# LilyPad_Rainbow_LED_v02.net
KiCad netlist of a schematic drawn in EAGLE
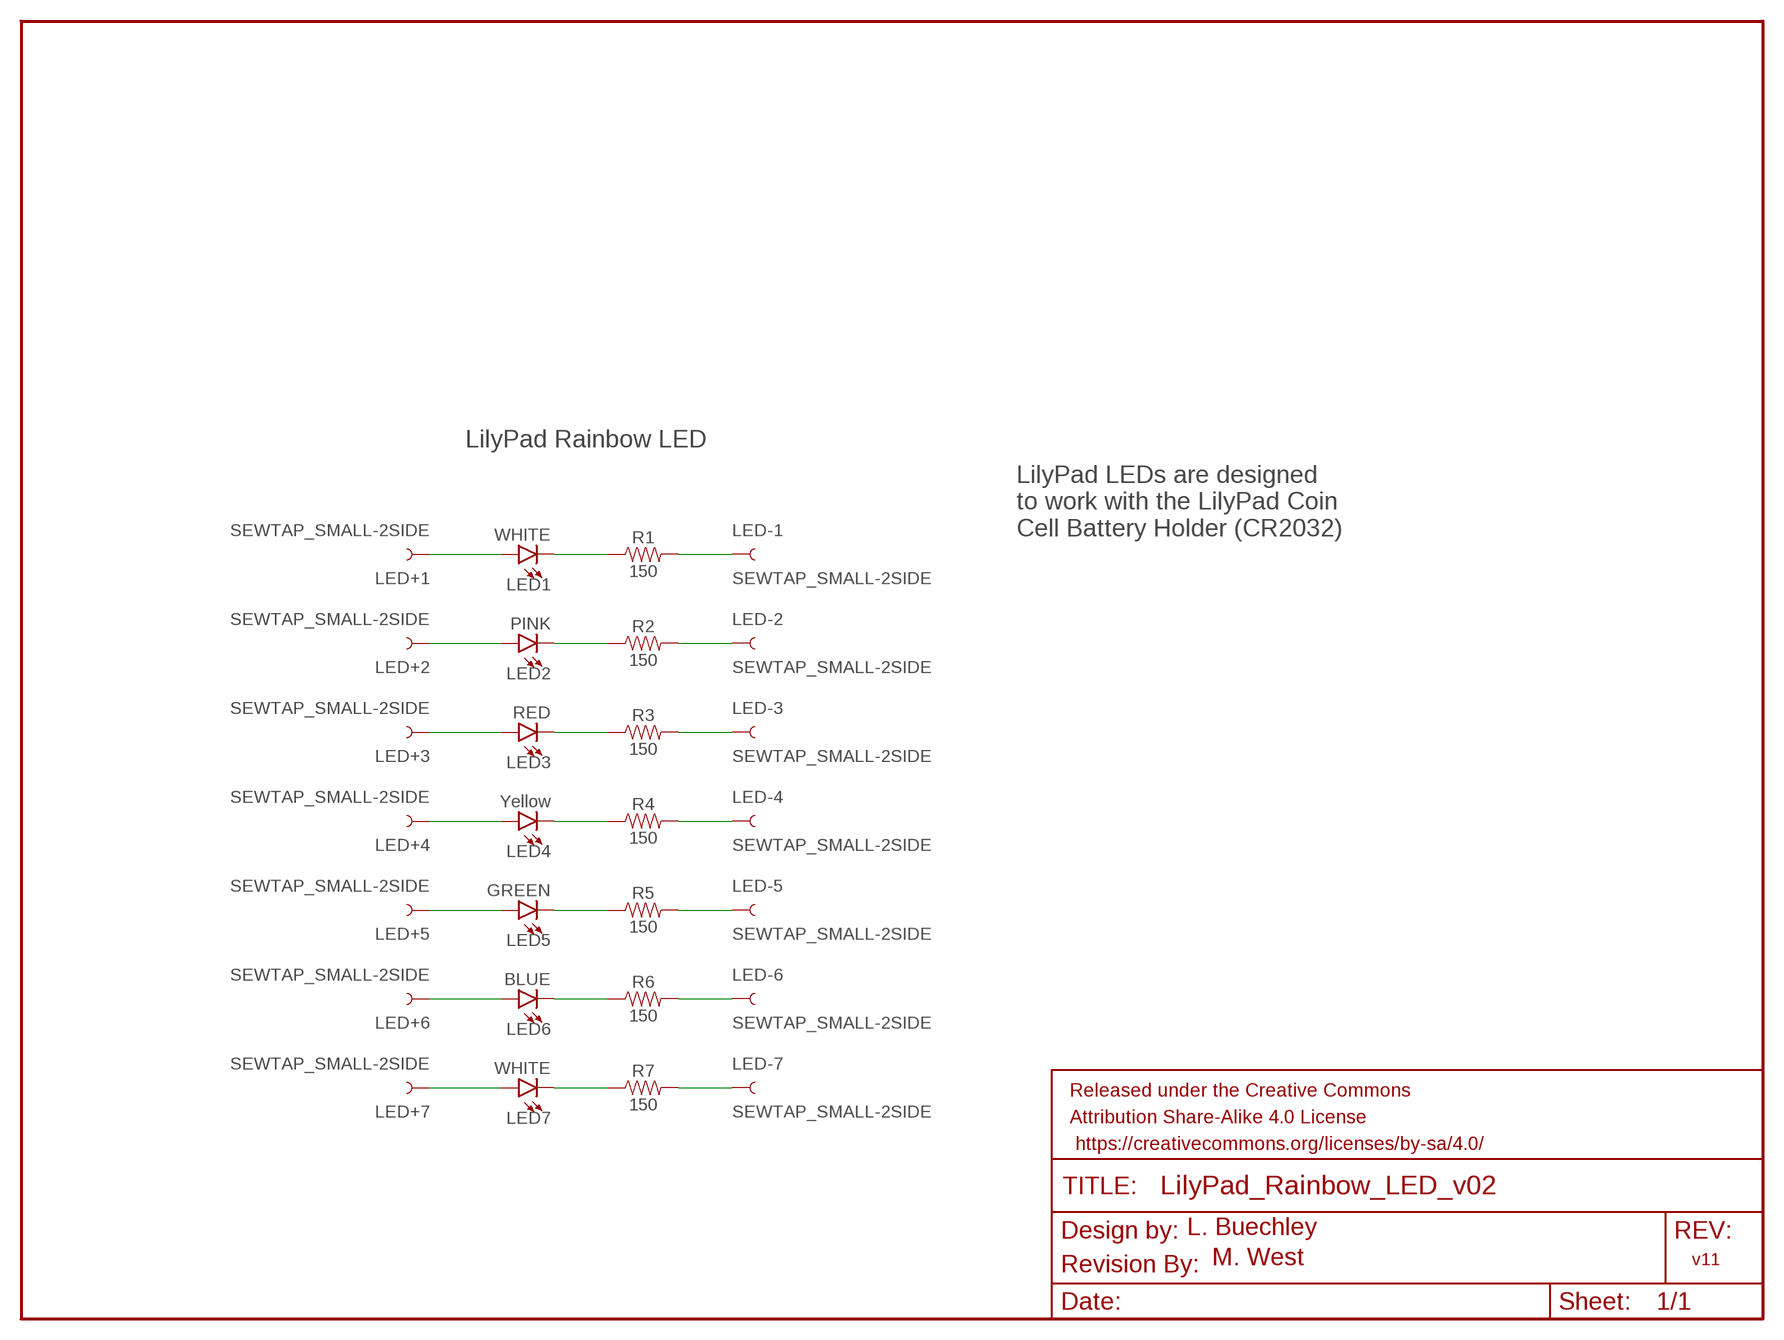
[diagram p0: schematic, sheet 1]

(export (version "E")
  (design (tool "Eeschema 10.0.6"))
  (components
    (comp (ref "FRAME1")
      (value "FRAME-LETTER")
      (footprint "eagle-import:CREATIVE_COMMONS")
      (libsource (lib "eagle-import") (part "FRAME-LETTER"))
    )
    (comp (ref "LED+1")
      (value "SEWTAP_SMALL-2SIDE")
      (footprint "eagle-import:PETAL-SMALL-2SIDE")
      (libsource (lib "eagle-import") (part "SEWTAP_SMALL-2SIDE"))
    )
    (comp (ref "LED+2")
      (value "SEWTAP_SMALL-2SIDE")
      (footprint "eagle-import:PETAL-SMALL-2SIDE")
      (libsource (lib "eagle-import") (part "SEWTAP_SMALL-2SIDE"))
    )
    (comp (ref "LED+3")
      (value "SEWTAP_SMALL-2SIDE")
      (footprint "eagle-import:PETAL-SMALL-2SIDE")
      (libsource (lib "eagle-import") (part "SEWTAP_SMALL-2SIDE"))
    )
    (comp (ref "LED+4")
      (value "SEWTAP_SMALL-2SIDE")
      (footprint "eagle-import:PETAL-SMALL-2SIDE")
      (libsource (lib "eagle-import") (part "SEWTAP_SMALL-2SIDE"))
    )
    (comp (ref "LED+5")
      (value "SEWTAP_SMALL-2SIDE")
      (footprint "eagle-import:PETAL-SMALL-2SIDE")
      (libsource (lib "eagle-import") (part "SEWTAP_SMALL-2SIDE"))
    )
    (comp (ref "LED+6")
      (value "SEWTAP_SMALL-2SIDE")
      (footprint "eagle-import:PETAL-SMALL-2SIDE")
      (libsource (lib "eagle-import") (part "SEWTAP_SMALL-2SIDE"))
    )
    (comp (ref "LED+7")
      (value "SEWTAP_SMALL-2SIDE")
      (footprint "eagle-import:PETAL-SMALL-2SIDE")
      (libsource (lib "eagle-import") (part "SEWTAP_SMALL-2SIDE"))
    )
    (comp (ref "LED-1")
      (value "SEWTAP_SMALL-2SIDE")
      (footprint "eagle-import:PETAL-SMALL-2SIDE")
      (libsource (lib "eagle-import") (part "SEWTAP_SMALL-2SIDE"))
    )
    (comp (ref "LED-2")
      (value "SEWTAP_SMALL-2SIDE")
      (footprint "eagle-import:PETAL-SMALL-2SIDE")
      (libsource (lib "eagle-import") (part "SEWTAP_SMALL-2SIDE"))
    )
    (comp (ref "LED-3")
      (value "SEWTAP_SMALL-2SIDE")
      (footprint "eagle-import:PETAL-SMALL-2SIDE")
      (libsource (lib "eagle-import") (part "SEWTAP_SMALL-2SIDE"))
    )
    (comp (ref "LED-4")
      (value "SEWTAP_SMALL-2SIDE")
      (footprint "eagle-import:PETAL-SMALL-2SIDE")
      (libsource (lib "eagle-import") (part "SEWTAP_SMALL-2SIDE"))
    )
    (comp (ref "LED-5")
      (value "SEWTAP_SMALL-2SIDE")
      (footprint "eagle-import:PETAL-SMALL-2SIDE")
      (libsource (lib "eagle-import") (part "SEWTAP_SMALL-2SIDE"))
    )
    (comp (ref "LED-6")
      (value "SEWTAP_SMALL-2SIDE")
      (footprint "eagle-import:PETAL-SMALL-2SIDE")
      (libsource (lib "eagle-import") (part "SEWTAP_SMALL-2SIDE"))
    )
    (comp (ref "LED-7")
      (value "SEWTAP_SMALL-2SIDE")
      (footprint "eagle-import:PETAL-SMALL-2SIDE")
      (libsource (lib "eagle-import") (part "SEWTAP_SMALL-2SIDE"))
    )
    (comp (ref "LED1")
      (value "WHITE")
      (footprint "eagle-import:LED-1206")
      (libsource (lib "eagle-import") (part "LED-WHITE1206"))
    )
    (comp (ref "LED2")
      (value "PINK")
      (footprint "eagle-import:LED-1206")
      (libsource (lib "eagle-import") (part "LED-PINK1206"))
    )
    (comp (ref "LED3")
      (value "RED")
      (footprint "eagle-import:LED-1206")
      (libsource (lib "eagle-import") (part "LED-RED1206"))
    )
    (comp (ref "LED4")
      (value "Yellow")
      (footprint "eagle-import:LED-1206")
      (libsource (lib "eagle-import") (part "LED-YELLOWLILYPAD"))
    )
    (comp (ref "LED5")
      (value "GREEN")
      (footprint "eagle-import:LED-1206")
      (libsource (lib "eagle-import") (part "LED-GREENLILYPAD"))
    )
    (comp (ref "LED6")
      (value "BLUE")
      (footprint "eagle-import:LED-1206")
      (libsource (lib "eagle-import") (part "LED-BLUE1206"))
    )
    (comp (ref "LED7")
      (value "WHITE")
      (footprint "eagle-import:LED-1206")
      (libsource (lib "eagle-import") (part "LED-WHITE1206"))
    )
    (comp (ref "R1")
      (value "150")
      (footprint "eagle-import:0603")
      (libsource (lib "eagle-import") (part "150OHM-0603-1/10W-1%"))
    )
    (comp (ref "R2")
      (value "150")
      (footprint "eagle-import:0603")
      (libsource (lib "eagle-import") (part "150OHM-0603-1/10W-1%"))
    )
    (comp (ref "R3")
      (value "150")
      (footprint "eagle-import:0603")
      (libsource (lib "eagle-import") (part "150OHM-0603-1/10W-1%"))
    )
    (comp (ref "R4")
      (value "150")
      (footprint "eagle-import:0603")
      (libsource (lib "eagle-import") (part "150OHM-0603-1/10W-1%"))
    )
    (comp (ref "R5")
      (value "150")
      (footprint "eagle-import:0603")
      (libsource (lib "eagle-import") (part "150OHM-0603-1/10W-1%"))
    )
    (comp (ref "R6")
      (value "150")
      (footprint "eagle-import:0603")
      (libsource (lib "eagle-import") (part "150OHM-0603-1/10W-1%"))
    )
    (comp (ref "R7")
      (value "150")
      (footprint "eagle-import:0603")
      (libsource (lib "eagle-import") (part "150OHM-0603-1/10W-1%"))
    )
    (comp (ref "U$1")
      (value "REVISION")
      (footprint "eagle-import:REVISION")
      (libsource (lib "eagle-import") (part "REVISION"))
    )
  )
  (nets
    (net (code "1") (name "Net-(LED+1-Pad1)") (class "Default")
      (node (ref "LED+1") (pin "1") (pinfunction "1_1") (pintype "bidirectional"))
      (node (ref "LED1") (pin "A") (pinfunction "A_A") (pintype "passive"))
    )
    (net (code "2") (name "Net-(LED+2-Pad1)") (class "Default")
      (node (ref "LED+2") (pin "1") (pinfunction "1_1") (pintype "bidirectional"))
      (node (ref "LED2") (pin "A") (pinfunction "A_A") (pintype "passive"))
    )
    (net (code "3") (name "Net-(LED+3-Pad1)") (class "Default")
      (node (ref "LED+3") (pin "1") (pinfunction "1_1") (pintype "bidirectional"))
      (node (ref "LED3") (pin "A") (pinfunction "A_A") (pintype "passive"))
    )
    (net (code "4") (name "Net-(LED+4-Pad1)") (class "Default")
      (node (ref "LED+4") (pin "1") (pinfunction "1_1") (pintype "bidirectional"))
      (node (ref "LED4") (pin "A") (pinfunction "A_A") (pintype "passive"))
    )
    (net (code "5") (name "Net-(LED+5-Pad1)") (class "Default")
      (node (ref "LED+5") (pin "1") (pinfunction "1_1") (pintype "bidirectional"))
      (node (ref "LED5") (pin "A") (pinfunction "A_A") (pintype "passive"))
    )
    (net (code "6") (name "Net-(LED+6-Pad1)") (class "Default")
      (node (ref "LED+6") (pin "1") (pinfunction "1_1") (pintype "bidirectional"))
      (node (ref "LED6") (pin "A") (pinfunction "A_A") (pintype "passive"))
    )
    (net (code "7") (name "Net-(LED+7-Pad1)") (class "Default")
      (node (ref "LED+7") (pin "1") (pinfunction "1_1") (pintype "bidirectional"))
      (node (ref "LED7") (pin "A") (pinfunction "A_A") (pintype "passive"))
    )
    (net (code "8") (name "Net-(LED-1-Pad1)") (class "Default")
      (node (ref "LED-1") (pin "1") (pinfunction "1_1") (pintype "bidirectional"))
      (node (ref "R1") (pin "2") (pinfunction "2_2") (pintype "passive"))
    )
    (net (code "9") (name "Net-(LED-2-Pad1)") (class "Default")
      (node (ref "LED-2") (pin "1") (pinfunction "1_1") (pintype "bidirectional"))
      (node (ref "R2") (pin "2") (pinfunction "2_2") (pintype "passive"))
    )
    (net (code "10") (name "Net-(LED-3-Pad1)") (class "Default")
      (node (ref "LED-3") (pin "1") (pinfunction "1_1") (pintype "bidirectional"))
      (node (ref "R3") (pin "2") (pinfunction "2_2") (pintype "passive"))
    )
    (net (code "11") (name "Net-(LED-4-Pad1)") (class "Default")
      (node (ref "LED-4") (pin "1") (pinfunction "1_1") (pintype "bidirectional"))
      (node (ref "R4") (pin "2") (pinfunction "2_2") (pintype "passive"))
    )
    (net (code "12") (name "Net-(LED-5-Pad1)") (class "Default")
      (node (ref "LED-5") (pin "1") (pinfunction "1_1") (pintype "bidirectional"))
      (node (ref "R5") (pin "2") (pinfunction "2_2") (pintype "passive"))
    )
    (net (code "13") (name "Net-(LED-6-Pad1)") (class "Default")
      (node (ref "LED-6") (pin "1") (pinfunction "1_1") (pintype "bidirectional"))
      (node (ref "R6") (pin "2") (pinfunction "2_2") (pintype "passive"))
    )
    (net (code "14") (name "Net-(LED-7-Pad1)") (class "Default")
      (node (ref "LED-7") (pin "1") (pinfunction "1_1") (pintype "bidirectional"))
      (node (ref "R7") (pin "2") (pinfunction "2_2") (pintype "passive"))
    )
    (net (code "15") (name "Net-(LED1-PadC)") (class "Default")
      (node (ref "LED1") (pin "C") (pinfunction "C_C") (pintype "passive"))
      (node (ref "R1") (pin "1") (pinfunction "1_1") (pintype "passive"))
    )
    (net (code "16") (name "Net-(LED2-PadC)") (class "Default")
      (node (ref "LED2") (pin "C") (pinfunction "C_C") (pintype "passive"))
      (node (ref "R2") (pin "1") (pinfunction "1_1") (pintype "passive"))
    )
    (net (code "17") (name "Net-(LED3-PadC)") (class "Default")
      (node (ref "LED3") (pin "C") (pinfunction "C_C") (pintype "passive"))
      (node (ref "R3") (pin "1") (pinfunction "1_1") (pintype "passive"))
    )
    (net (code "18") (name "Net-(LED4-PadC)") (class "Default")
      (node (ref "LED4") (pin "C") (pinfunction "C_C") (pintype "passive"))
      (node (ref "R4") (pin "1") (pinfunction "1_1") (pintype "passive"))
    )
    (net (code "19") (name "Net-(LED5-PadC)") (class "Default")
      (node (ref "LED5") (pin "C") (pinfunction "C_C") (pintype "passive"))
      (node (ref "R5") (pin "1") (pinfunction "1_1") (pintype "passive"))
    )
    (net (code "20") (name "Net-(LED6-PadC)") (class "Default")
      (node (ref "LED6") (pin "C") (pinfunction "C_C") (pintype "passive"))
      (node (ref "R6") (pin "1") (pinfunction "1_1") (pintype "passive"))
    )
    (net (code "21") (name "Net-(LED7-PadC)") (class "Default")
      (node (ref "LED7") (pin "C") (pinfunction "C_C") (pintype "passive"))
      (node (ref "R7") (pin "1") (pinfunction "1_1") (pintype "passive"))
    )
  )
)
